# routeur_wemos_Maxi_v1_1c_2020-05-14_15-5.net
KiCad netlist of a schematic drawn in EasyEDA
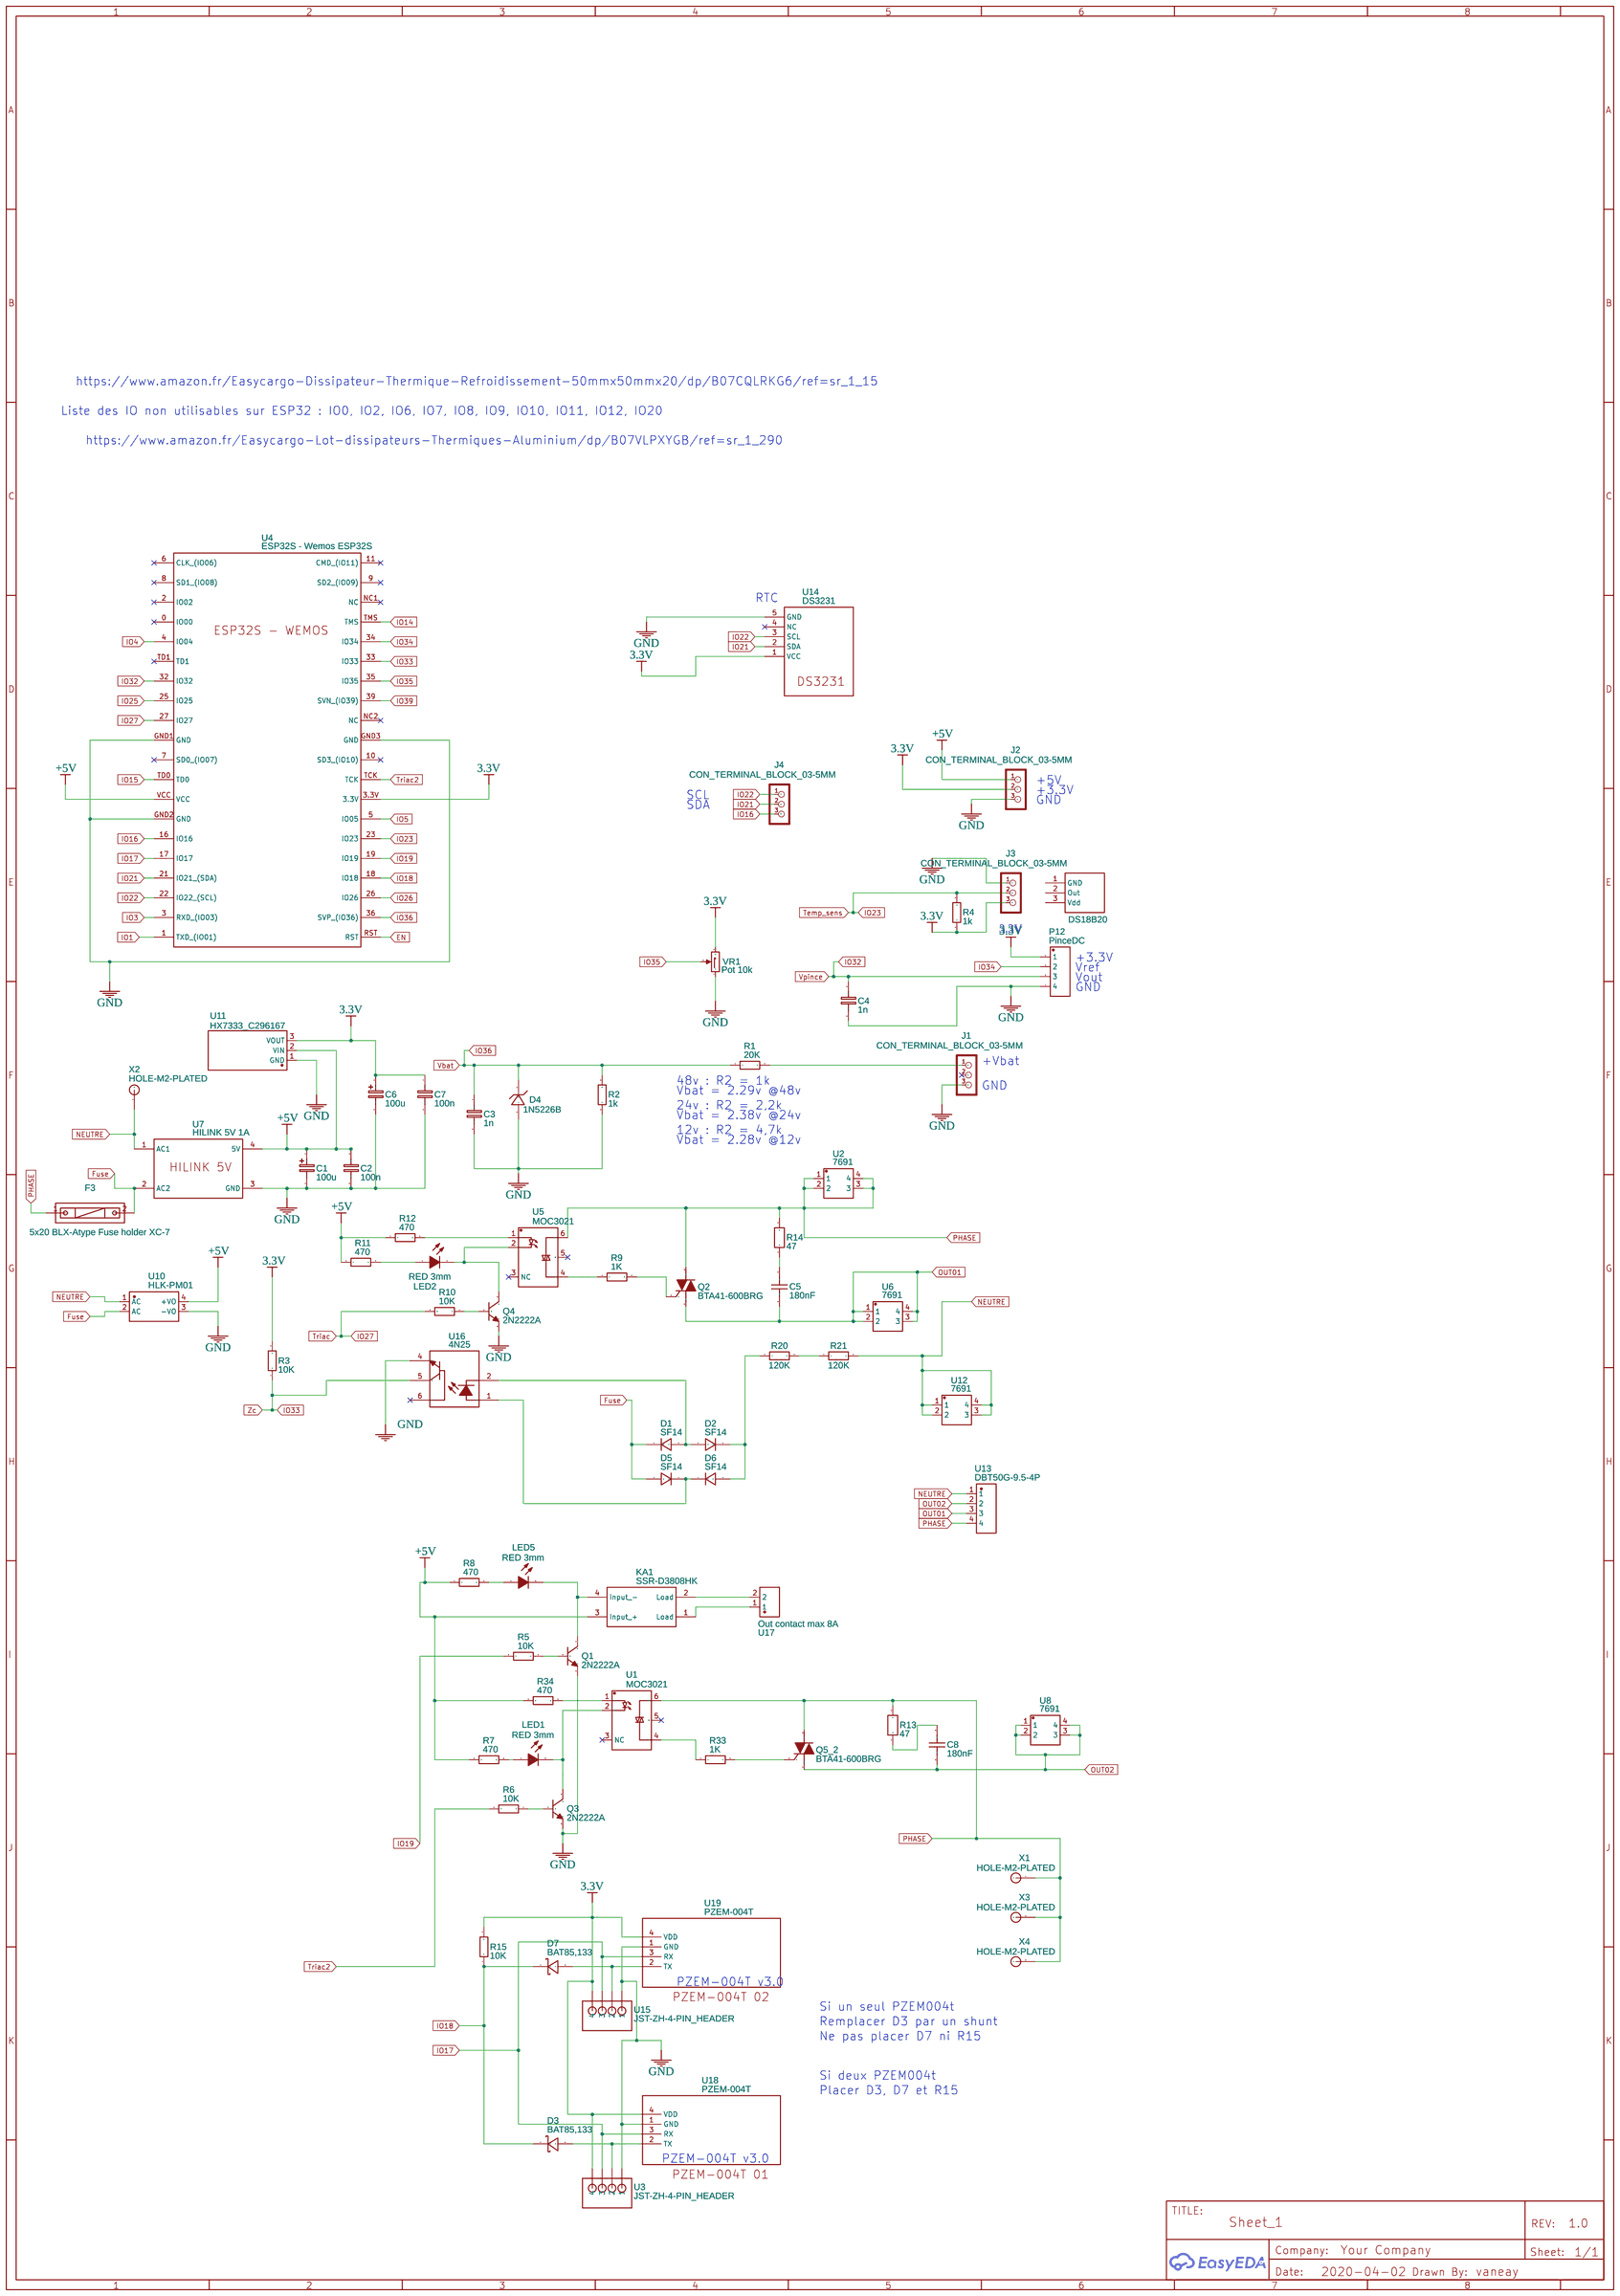
[diagram p0: schematic sheet]

(export (version "E")
  (design (tool "Eeschema 10.0.6"))
  (components
    (comp (ref "C1")
      (value "100u")
      (fields (field (name "BOM_Supplier Part") "C122609"))
      (libsource (lib "") (part "Cap_Electrolytic(TH)_D3.0XF1.5_EU"))
    )
    (comp (ref "C2")
      (value "100n")
      (fields (field (name "BOM_Supplier Part") "C94717"))
      (libsource (lib "") (part "Cap_RAD-0.1_EU"))
    )
    (comp (ref "C3")
      (value "1n")
      (fields (field (name "BOM_Supplier Part") "C192448"))
      (libsource (lib "") (part "Cap_RAD-0.1_EU"))
    )
    (comp (ref "C4")
      (value "1n")
      (fields (field (name "BOM_Supplier Part") "C192448"))
      (libsource (lib "") (part "Cap_RAD-0.1_EU_1"))
    )
    (comp (ref "C5")
      (value "180nF")
      (fields
        (field (name "BOM_Manufacturer Part") "SMXDX184KD2XXAB1515")
        (field (name "BOM_Supplier Part") "C155792")
      )
      (libsource (lib "") (part "SMXDX184KD2XXAB1515"))
    )
    (comp (ref "C6")
      (value "100u")
      (fields (field (name "BOM_Supplier Part") "C122609"))
      (libsource (lib "") (part "Cap_Electrolytic(TH)_D3.0XF1.5_EU"))
    )
    (comp (ref "C7")
      (value "100n")
      (fields (field (name "BOM_Supplier Part") "C94717"))
      (libsource (lib "") (part "Cap_RAD-0.1_EU"))
    )
    (comp (ref "C8")
      (value "180nF")
      (fields
        (field (name "BOM_Manufacturer Part") "SMXDX184KD2XXAB1515")
        (field (name "BOM_Supplier Part") "C155792")
      )
      (libsource (lib "") (part "SMXDX184KD2XXAB1515"))
    )
    (comp (ref "D1")
      (value "SF14")
      (fields (field (name "BOM_Supplier Part") "C331690"))
      (libsource (lib "") (part "SF14_1"))
    )
    (comp (ref "D2")
      (value "SF14")
      (fields (field (name "BOM_Supplier Part") "C331690"))
      (libsource (lib "") (part "SF14"))
    )
    (comp (ref "D3")
      (value "BAT85,133")
      (fields (field (name "BOM_Supplier Part") "C134301"))
      (libsource (lib "") (part "BAT85,133"))
    )
    (comp (ref "D4")
      (value "1N5226B")
      (fields (field (name "BOM_Supplier Part") "C51291"))
      (libsource (lib "") (part "1N751A"))
    )
    (comp (ref "D5")
      (value "SF14")
      (fields (field (name "BOM_Supplier Part") "C331690"))
      (libsource (lib "") (part "SF14"))
    )
    (comp (ref "D6")
      (value "SF14")
      (fields (field (name "BOM_Supplier Part") "C331690"))
      (libsource (lib "") (part "SF14_1"))
    )
    (comp (ref "D7")
      (value "BAT85,133")
      (fields (field (name "BOM_Supplier Part") "C134301"))
      (libsource (lib "") (part "BAT85,133"))
    )
    (comp (ref "F3")
      (value "5x20 BLX-Atype Fuse holder XC-7")
      (fields (field (name "BOM_Supplier Part") "C3131"))
      (libsource (lib "") (part "5x20 BLX-Atype Fuse holder XC-7"))
    )
    (comp (ref "J1")
      (value "CON_TERMINAL_BLOCK_03-5MM")
      (fields (field (name "BOM_Manufacturer Part") "?") (field (name "BOM_Supplier Part") "C182803"))
      (libsource (lib "") (part "Unknown_985_-425"))
    )
    (comp (ref "J2")
      (value "CON_TERMINAL_BLOCK_03-5MM")
      (fields (field (name "BOM_Manufacturer Part") "?") (field (name "BOM_Supplier Part") "C182803"))
      (libsource (lib "") (part "Unknown_1035_-715"))
    )
    (comp (ref "J3")
      (value "CON_TERMINAL_BLOCK_03-5MM")
      (fields (field (name "BOM_Manufacturer Part") "?") (field (name "BOM_Supplier Part") "C182803"))
      (libsource (lib "") (part "Unknown_1030_-610"))
    )
    (comp (ref "J4")
      (value "CON_TERMINAL_BLOCK_03-5MM")
      (fields (field (name "BOM_Manufacturer Part") "?") (field (name "BOM_Supplier Part") "C182803"))
      (libsource (lib "") (part "Unknown_795_-700"))
    )
    (comp (ref "KA1") (value "SSR-D3808HK") (libsource (lib "") (part "SSR-D3808HK")))
    (comp (ref "LED1")
      (value "RED 3mm")
      (fields
        (field (name "BOM_Manufacturer Part") "204-10SURD/S530-A3-L")
        (field (name "BOM_Supplier Part") "C99771")
      )
      (libsource (lib "") (part "204-10SURD/S530-A3-L"))
    )
    (comp (ref "LED2")
      (value "RED 3mm")
      (fields
        (field (name "BOM_Manufacturer Part") "204-10SURD/S530-A3-L")
        (field (name "BOM_Supplier Part") "C99771")
      )
      (libsource (lib "") (part "204-10SURD/S530-A3-L"))
    )
    (comp (ref "LED5")
      (value "RED 3mm")
      (fields
        (field (name "BOM_Manufacturer Part") "204-10SURD/S530-A3-L")
        (field (name "BOM_Supplier Part") "C99771")
      )
      (libsource (lib "") (part "204-10SURD/S530-A3-L"))
    )
    (comp (ref "P12")
      (value "PinceDC")
      (fields
        (field (name "BOM_Manufacturer Part") "EK508V-04P")
        (field (name "BOM_Supplier Part") "C182807")
      )
      (libsource (lib "") (part "WJ2EDGVC-5.08-4P"))
    )
    (comp (ref "Q1")
      (value "2N2222A")
      (fields (field (name "BOM_Supplier Part") "C358533"))
      (libsource (lib "") (part "2N2222A"))
    )
    (comp (ref "Q2")
      (value "BTA41-600BRG")
      (fields (field (name "BOM_Supplier Part") "C9103"))
      (libsource (lib "") (part "BTA41-600BRG"))
    )
    (comp (ref "Q3")
      (value "2N2222A")
      (fields (field (name "BOM_Supplier Part") "C358533"))
      (libsource (lib "") (part "2N2222A"))
    )
    (comp (ref "Q4")
      (value "2N2222A")
      (fields (field (name "BOM_Supplier Part") "C358533"))
      (libsource (lib "") (part "2N2222A"))
    )
    (comp (ref "Q5_2")
      (value "BTA41-600BRG")
      (fields (field (name "BOM_Supplier Part") "C9103"))
      (libsource (lib "") (part "BTA41-600BRG_1"))
    )
    (comp (ref "R1")
      (value "20K")
      (fields (field (name "BOM_Supplier Part") "C58592"))
      (libsource (lib "") (part "0805_2"))
    )
    (comp (ref "R2")
      (value "1k")
      (fields (field (name "BOM_Supplier Part") "C58592"))
      (libsource (lib "") (part "0805"))
    )
    (comp (ref "R3")
      (value "10K")
      (fields (field (name "BOM_Supplier Part") "C57436"))
      (libsource (lib "") (part "0805"))
    )
    (comp (ref "R4")
      (value "1k")
      (fields (field (name "BOM_Supplier Part") "C58592"))
      (libsource (lib "") (part "0805"))
    )
    (comp (ref "R5")
      (value "10K")
      (fields (field (name "BOM_Supplier Part") "C57436"))
      (libsource (lib "") (part "0805_1"))
    )
    (comp (ref "R6")
      (value "10K")
      (fields (field (name "BOM_Supplier Part") "C57436"))
      (libsource (lib "") (part "0805_1"))
    )
    (comp (ref "R7")
      (value "470")
      (fields (field (name "BOM_Supplier Part") "C58592"))
      (libsource (lib "") (part "0805_2"))
    )
    (comp (ref "R8")
      (value "470")
      (fields (field (name "BOM_Supplier Part") "C58592"))
      (libsource (lib "") (part "0805_2"))
    )
    (comp (ref "R9")
      (value "1K")
      (fields (field (name "BOM_Supplier Part") "C385291"))
      (libsource (lib "") (part "MFR1WSJT-52-5K1"))
    )
    (comp (ref "R10")
      (value "10K")
      (fields (field (name "BOM_Supplier Part") "C57436"))
      (libsource (lib "") (part "0805_1"))
    )
    (comp (ref "R11")
      (value "470")
      (fields (field (name "BOM_Supplier Part") "C58592"))
      (libsource (lib "") (part "0805_2"))
    )
    (comp (ref "R12")
      (value "470")
      (fields (field (name "BOM_Supplier Part") "C58592"))
      (libsource (lib "") (part "0805_2"))
    )
    (comp (ref "R13")
      (value "47")
      (fields
        (field (name "BOM_Manufacturer Part") "RN 2WS 47R F T/B A1")
        (field (name "BOM_Supplier Part") "C433590")
      )
      (libsource (lib "") (part "RN 2WS 47R F T/B A1"))
    )
    (comp (ref "R14")
      (value "47")
      (fields
        (field (name "BOM_Manufacturer Part") "RN 2WS 47R F T/B A1")
        (field (name "BOM_Supplier Part") "C433590")
      )
      (libsource (lib "") (part "RN 2WS 47R F T/B A1"))
    )
    (comp (ref "R15")
      (value "10K")
      (fields (field (name "BOM_Supplier Part") "C57436"))
      (libsource (lib "") (part "0805"))
    )
    (comp (ref "R20")
      (value "120K")
      (fields (field (name "BOM_Supplier Part") "C433673"))
      (libsource (lib "") (part "MFR1WSJT-52-5K1"))
    )
    (comp (ref "R21")
      (value "120K")
      (fields (field (name "BOM_Supplier Part") "C433673"))
      (libsource (lib "") (part "MFR1WSJT-52-5K1"))
    )
    (comp (ref "R33")
      (value "1K")
      (fields (field (name "BOM_Supplier Part") "C385291"))
      (libsource (lib "") (part "MFR1WSJT-52-5K1"))
    )
    (comp (ref "R34")
      (value "470")
      (fields (field (name "BOM_Supplier Part") "C58592"))
      (libsource (lib "") (part "0805_2"))
    )
    (comp (ref "U1")
      (value "MOC3021")
      (fields (field (name "BOM_Supplier Part") "C123202"))
      (libsource (lib "") (part "MOC3021"))
    )
    (comp (ref "U2")
      (value "7691")
      (fields (field (name "BOM_Supplier Part") "C238163"))
      (libsource (lib "") (part "7691"))
    )
    (comp (ref "U3")
      (value "JST-ZH-4-PIN_HEADER")
      (fields (field (name "BOM_Supplier Part") "C163034"))
      (libsource (lib "") (part "JST-ZH-4-PIN_HEADER"))
    )
    (comp (ref "U4")
      (value "ESP32S - Wemos ESP32S")
      (fields (field (name "BOM_Manufacturer Part") "ESP32S"))
      (libsource (lib "") (part "ESP32S - Wemos ESP32S"))
    )
    (comp (ref "U5")
      (value "MOC3021")
      (fields (field (name "BOM_Supplier Part") "C123202"))
      (libsource (lib "") (part "MOC3021_1"))
    )
    (comp (ref "U6")
      (value "7691")
      (fields (field (name "BOM_Supplier Part") "C238163"))
      (libsource (lib "") (part "7691"))
    )
    (comp (ref "U7")
      (value "HILINK 5V 1A")
      (fields (field (name "BOM_Manufacturer Part") "HLK-5M05") (field (name "BOM_Supplier Part") "C209907"))
      (libsource (lib "") (part "HILINK 5V corrected"))
    )
    (comp (ref "U8")
      (value "7691")
      (fields (field (name "BOM_Supplier Part") "C238163"))
      (libsource (lib "") (part "7691"))
    )
    (comp (ref "U9") (value "DS18B20") (libsource (lib "") (part "DS18B20")))
    (comp (ref "U10")
      (value "HLK-PM01")
      (fields (field (name "BOM_Supplier Part") "C209903"))
      (libsource (lib "") (part "HLK-PM01"))
    )
    (comp (ref "U11")
      (value "HX7333_C296167")
      (fields (field (name "BOM_Manufacturer Part") "HX7333") (field (name "BOM_Supplier Part") "C296167"))
      (libsource (lib "") (part "HX7333_C296167"))
    )
    (comp (ref "U12")
      (value "7691")
      (fields (field (name "BOM_Supplier Part") "C238163"))
      (libsource (lib "") (part "7691"))
    )
    (comp (ref "U13")
      (value "DBT50G-9.5-4P")
      (fields (field (name "BOM_Supplier Part") "C395960"))
      (libsource (lib "") (part "DBT50G-9.5-4P"))
    )
    (comp (ref "U14")
      (value "DS3231")
      (fields
        (field (name "BOM_Supplier Part") "https://www.amazon.fr/Delicacydex-dhorloge-arduino-Batterie-Raspberry/dp/B07P6RHHKX/ref=sr_1_2")
      )
      (libsource (lib "") (part "DS3231"))
    )
    (comp (ref "U15")
      (value "JST-ZH-4-PIN_HEADER")
      (fields (field (name "BOM_Supplier Part") "C163034"))
      (libsource (lib "") (part "JST-ZH-4-PIN_HEADER"))
    )
    (comp (ref "U16")
      (value "4N25")
      (fields (field (name "BOM_Supplier Part") "C115480"))
      (libsource (lib "") (part "4N25"))
    )
    (comp (ref "U17")
      (value "Out contact max 8A")
      (fields (field (name "BOM_Manufacturer Part") "282858-2") (field (name "BOM_Supplier Part") "C306150"))
      (libsource (lib "") (part "282858-2"))
    )
    (comp (ref "U18")
      (value "PZEM-004T")
      (fields (field (name "BOM_Manufacturer Part") "New SchematicLib"))
      (libsource (lib "") (part "PZEM-004T_1"))
    )
    (comp (ref "U19")
      (value "PZEM-004T")
      (fields (field (name "BOM_Manufacturer Part") "New SchematicLib"))
      (libsource (lib "") (part "PZEM-004T"))
    )
    (comp (ref "VR1") (value "Pot 10k") (libsource (lib "") (part "Pot")))
    (comp (ref "X1")
      (value "HOLE-M2-PLATED")
      (fields (field (name "BOM_Manufacturer Part") "New SchematicLib"))
      (libsource (lib "") (part "HOLE-M2-PLATED_1"))
    )
    (comp (ref "X2")
      (value "HOLE-M2-PLATED")
      (fields (field (name "BOM_Manufacturer Part") "New SchematicLib"))
      (libsource (lib "") (part "HOLE-M2-PLATED"))
    )
    (comp (ref "X3")
      (value "HOLE-M2-PLATED")
      (fields (field (name "BOM_Manufacturer Part") "New SchematicLib"))
      (libsource (lib "") (part "HOLE-M2-PLATED_1"))
    )
    (comp (ref "X4")
      (value "HOLE-M2-PLATED")
      (fields (field (name "BOM_Manufacturer Part") "New SchematicLib"))
      (libsource (lib "") (part "HOLE-M2-PLATED_1"))
    )
  )
  (nets
    (net (code "1") (name "+5V") (class "Default")
      (node (ref "C1") (pin "1") (pinfunction "1_1") (pintype "unspecified"))
      (node (ref "C2") (pin "1") (pinfunction "1_1") (pintype "unspecified"))
      (node (ref "J2") (pin "1") (pinfunction "1_1") (pintype "unspecified"))
      (node (ref "KA1") (pin "3") (pinfunction "Input_+_3") (pintype "unspecified"))
      (node (ref "R11") (pin "1") (pinfunction "1_1") (pintype "unspecified"))
      (node (ref "R12") (pin "1") (pinfunction "1_1") (pintype "unspecified"))
      (node (ref "R34") (pin "1") (pinfunction "1_1") (pintype "unspecified"))
      (node (ref "R7") (pin "1") (pinfunction "1_1") (pintype "unspecified"))
      (node (ref "R8") (pin "1") (pinfunction "1_1") (pintype "unspecified"))
      (node (ref "U10") (pin "4") (pinfunction "+VO_4") (pintype "unspecified"))
      (node (ref "U11") (pin "2") (pinfunction "VIN_2") (pintype "unspecified"))
      (node (ref "U4") (pin "VCC") (pinfunction "VCC_VCC") (pintype "unspecified"))
      (node (ref "U7") (pin "4") (pinfunction "5V_4") (pintype "unspecified"))
    )
    (net (code "2") (name "3.3V") (class "Default")
      (node (ref "C6") (pin "1") (pinfunction "1_1") (pintype "unspecified"))
      (node (ref "C7") (pin "1") (pinfunction "1_1") (pintype "unspecified"))
      (node (ref "J2") (pin "2") (pinfunction "2_2") (pintype "unspecified"))
      (node (ref "J3") (pin "3") (pinfunction "3_3") (pintype "unspecified"))
      (node (ref "P12") (pin "1") (pinfunction "1_1") (pintype "unspecified"))
      (node (ref "R15") (pin "2") (pinfunction "2_2") (pintype "unspecified"))
      (node (ref "R3") (pin "2") (pinfunction "2_2") (pintype "unspecified"))
      (node (ref "R4") (pin "1") (pinfunction "1_1") (pintype "unspecified"))
      (node (ref "U11") (pin "3") (pinfunction "VOUT_3") (pintype "unspecified"))
      (node (ref "U14") (pin "1") (pinfunction "VCC_1") (pintype "unspecified"))
      (node (ref "U15") (pin "P4") (pinfunction "4_P4") (pintype "unspecified"))
      (node (ref "U18") (pin "4") (pinfunction "VDD_4") (pintype "unspecified"))
      (node (ref "U19") (pin "4") (pinfunction "VDD_4") (pintype "unspecified"))
      (node (ref "U3") (pin "P4") (pinfunction "4_P4") (pintype "unspecified"))
      (node (ref "U4") (pin "3.3V") (pinfunction "3.3V_3.3V") (pintype "unspecified"))
      (node (ref "VR1") (pin "3") (pinfunction "3_3") (pintype "unspecified"))
    )
    (net (code "3") (name "EN") (class "Default")
      (node (ref "U4") (pin "RST") (pinfunction "RST_RST") (pintype "unspecified"))
    )
    (net (code "4") (name "Fuse") (class "Default")
      (node (ref "D1") (pin "1") (pinfunction "1_1") (pintype "unspecified"))
      (node (ref "D5") (pin "2") (pinfunction "2_2") (pintype "unspecified"))
      (node (ref "F3") (pin "2") (pinfunction "2_2") (pintype "unspecified"))
      (node (ref "U10") (pin "2") (pinfunction "AC_2") (pintype "unspecified"))
      (node (ref "U7") (pin "2") (pinfunction "AC2_2") (pintype "unspecified"))
    )
    (net (code "5") (name "GND") (class "Default")
      (node (ref "C1") (pin "2") (pinfunction "2_2") (pintype "unspecified"))
      (node (ref "C2") (pin "2") (pinfunction "2_2") (pintype "unspecified"))
      (node (ref "C3") (pin "2") (pinfunction "2_2") (pintype "unspecified"))
      (node (ref "C4") (pin "2") (pinfunction "2_2") (pintype "unspecified"))
      (node (ref "C6") (pin "2") (pinfunction "2_2") (pintype "unspecified"))
      (node (ref "C7") (pin "2") (pinfunction "2_2") (pintype "unspecified"))
      (node (ref "D4") (pin "2") (pinfunction "A_2") (pintype "unspecified"))
      (node (ref "J1") (pin "3") (pinfunction "3_3") (pintype "unspecified"))
      (node (ref "J2") (pin "3") (pinfunction "3_3") (pintype "unspecified"))
      (node (ref "J3") (pin "1") (pinfunction "1_1") (pintype "unspecified"))
      (node (ref "P12") (pin "4") (pinfunction "4_4") (pintype "unspecified"))
      (node (ref "Q1") (pin "3") (pinfunction "E_3") (pintype "unspecified"))
      (node (ref "Q3") (pin "3") (pinfunction "E_3") (pintype "unspecified"))
      (node (ref "Q4") (pin "3") (pinfunction "E_3") (pintype "unspecified"))
      (node (ref "R2") (pin "1") (pinfunction "1_1") (pintype "unspecified"))
      (node (ref "U10") (pin "3") (pinfunction "-VO_3") (pintype "unspecified"))
      (node (ref "U11") (pin "1") (pinfunction "GND_1") (pintype "unspecified"))
      (node (ref "U14") (pin "5") (pinfunction "GND_5") (pintype "unspecified"))
      (node (ref "U15") (pin "P1") (pinfunction "1_P1") (pintype "unspecified"))
      (node (ref "U16") (pin "4") (pinfunction "4_4") (pintype "unspecified"))
      (node (ref "U18") (pin "1") (pinfunction "GND_1") (pintype "unspecified"))
      (node (ref "U19") (pin "1") (pinfunction "GND_1") (pintype "unspecified"))
      (node (ref "U3") (pin "P1") (pinfunction "1_P1") (pintype "unspecified"))
      (node (ref "U4") (pin "GND1") (pinfunction "GND_GND1") (pintype "unspecified"))
      (node (ref "U4") (pin "GND2") (pinfunction "GND_GND2") (pintype "unspecified"))
      (node (ref "U4") (pin "GND3") (pinfunction "GND_GND3") (pintype "unspecified"))
      (node (ref "U7") (pin "3") (pinfunction "GND_3") (pintype "unspecified"))
      (node (ref "VR1") (pin "1") (pinfunction "1_1") (pintype "unspecified"))
    )
    (net (code "6") (name "IO1") (class "Default")
      (node (ref "U4") (pin "1") (pinfunction "TXD_(IO01)_1") (pintype "unspecified"))
    )
    (net (code "7") (name "IO3") (class "Default")
      (node (ref "U4") (pin "3") (pinfunction "RXD_(IO03)_3") (pintype "unspecified"))
    )
    (net (code "8") (name "IO4") (class "Default")
      (node (ref "U4") (pin "4") (pinfunction "IO04_4") (pintype "unspecified"))
    )
    (net (code "9") (name "IO5") (class "Default")
      (node (ref "U4") (pin "5") (pinfunction "IO05_5") (pintype "unspecified"))
    )
    (net (code "10") (name "IO14") (class "Default")
      (node (ref "U4") (pin "TMS") (pinfunction "TMS_TMS") (pintype "unspecified"))
    )
    (net (code "11") (name "IO15") (class "Default")
      (node (ref "U4") (pin "TD0") (pinfunction "TD0_TD0") (pintype "unspecified"))
    )
    (net (code "12") (name "IO16") (class "Default")
      (node (ref "J4") (pin "3") (pinfunction "3_3") (pintype "unspecified"))
      (node (ref "U4") (pin "16") (pinfunction "IO16_16") (pintype "unspecified"))
    )
    (net (code "13") (name "IO17") (class "Default")
      (node (ref "U15") (pin "P3") (pinfunction "3_P3") (pintype "unspecified"))
      (node (ref "U18") (pin "3") (pinfunction "RX_3") (pintype "unspecified"))
      (node (ref "U19") (pin "3") (pinfunction "RX_3") (pintype "unspecified"))
      (node (ref "U3") (pin "P3") (pinfunction "3_P3") (pintype "unspecified"))
      (node (ref "U4") (pin "17") (pinfunction "IO17_17") (pintype "unspecified"))
    )
    (net (code "14") (name "IO18") (class "Default")
      (node (ref "D3") (pin "1") (pinfunction "K_1") (pintype "unspecified"))
      (node (ref "D7") (pin "1") (pinfunction "K_1") (pintype "unspecified"))
      (node (ref "R15") (pin "1") (pinfunction "1_1") (pintype "unspecified"))
      (node (ref "U4") (pin "18") (pinfunction "IO18_18") (pintype "unspecified"))
    )
    (net (code "15") (name "IO19") (class "Default")
      (node (ref "R5") (pin "2") (pinfunction "2_2") (pintype "unspecified"))
      (node (ref "U4") (pin "19") (pinfunction "IO19_19") (pintype "unspecified"))
    )
    (net (code "16") (name "IO21") (class "Default")
      (node (ref "J4") (pin "2") (pinfunction "2_2") (pintype "unspecified"))
      (node (ref "U14") (pin "2") (pinfunction "SDA_2") (pintype "unspecified"))
      (node (ref "U4") (pin "21") (pinfunction "IO21_(SDA)_21") (pintype "unspecified"))
    )
    (net (code "17") (name "IO22") (class "Default")
      (node (ref "J4") (pin "1") (pinfunction "1_1") (pintype "unspecified"))
      (node (ref "U14") (pin "3") (pinfunction "SCL_3") (pintype "unspecified"))
      (node (ref "U4") (pin "22") (pinfunction "IO22_(SCL)_22") (pintype "unspecified"))
    )
    (net (code "18") (name "IO23") (class "Default")
      (node (ref "J3") (pin "2") (pinfunction "2_2") (pintype "unspecified"))
      (node (ref "R4") (pin "2") (pinfunction "2_2") (pintype "unspecified"))
      (node (ref "U4") (pin "23") (pinfunction "IO23_23") (pintype "unspecified"))
    )
    (net (code "19") (name "IO25") (class "Default")
      (node (ref "U4") (pin "25") (pinfunction "IO25_25") (pintype "unspecified"))
    )
    (net (code "20") (name "IO26") (class "Default")
      (node (ref "U4") (pin "26") (pinfunction "IO26_26") (pintype "unspecified"))
    )
    (net (code "21") (name "IO27") (class "Default")
      (node (ref "R10") (pin "2") (pinfunction "2_2") (pintype "unspecified"))
      (node (ref "U4") (pin "27") (pinfunction "IO27_27") (pintype "unspecified"))
    )
    (net (code "22") (name "IO32") (class "Default")
      (node (ref "C4") (pin "1") (pinfunction "1_1") (pintype "unspecified"))
      (node (ref "P12") (pin "3") (pinfunction "3_3") (pintype "unspecified"))
      (node (ref "U4") (pin "32") (pinfunction "IO32_32") (pintype "unspecified"))
    )
    (net (code "23") (name "IO33") (class "Default")
      (node (ref "R3") (pin "1") (pinfunction "1_1") (pintype "unspecified"))
      (node (ref "U16") (pin "5") (pinfunction "5_5") (pintype "unspecified"))
      (node (ref "U4") (pin "33") (pinfunction "IO33_33") (pintype "unspecified"))
    )
    (net (code "24") (name "IO34") (class "Default")
      (node (ref "P12") (pin "2") (pinfunction "2_2") (pintype "unspecified"))
      (node (ref "U4") (pin "34") (pinfunction "IO34_34") (pintype "unspecified"))
    )
    (net (code "25") (name "IO35") (class "Default")
      (node (ref "U4") (pin "35") (pinfunction "IO35_35") (pintype "unspecified"))
      (node (ref "VR1") (pin "2") (pinfunction "2_2") (pintype "unspecified"))
    )
    (net (code "26") (name "IO36") (class "Default")
      (node (ref "C3") (pin "1") (pinfunction "1_1") (pintype "unspecified"))
      (node (ref "D4") (pin "1") (pinfunction "C_1") (pintype "unspecified"))
      (node (ref "R1") (pin "1") (pinfunction "1_1") (pintype "unspecified"))
      (node (ref "R2") (pin "2") (pinfunction "2_2") (pintype "unspecified"))
      (node (ref "U4") (pin "36") (pinfunction "SVP_(IO36)_36") (pintype "unspecified"))
    )
    (net (code "27") (name "IO39") (class "Default")
      (node (ref "U4") (pin "39") (pinfunction "SVN_(IO39)_39") (pintype "unspecified"))
    )
    (net (code "28") (name "NEUTRE") (class "Default")
      (node (ref "R21") (pin "2") (pinfunction "2_2") (pintype "unspecified"))
      (node (ref "U10") (pin "1") (pinfunction "AC_1") (pintype "unspecified"))
      (node (ref "U12") (pin "1") (pinfunction "1_1") (pintype "unspecified"))
      (node (ref "U12") (pin "2") (pinfunction "2_2") (pintype "unspecified"))
      (node (ref "U12") (pin "3") (pinfunction "3_3") (pintype "unspecified"))
      (node (ref "U12") (pin "4") (pinfunction "4_4") (pintype "unspecified"))
      (node (ref "U13") (pin "1") (pinfunction "1_1") (pintype "unspecified"))
      (node (ref "U7") (pin "1") (pinfunction "AC1_1") (pintype "unspecified"))
      (node (ref "X2") (pin "1") (pinfunction "1_1") (pintype "unspecified"))
    )
    (net (code "29") (name "Net-(C5-Pad1)") (class "Default")
      (node (ref "C5") (pin "1") (pinfunction "1_1") (pintype "unspecified"))
      (node (ref "R14") (pin "1") (pinfunction "1_1") (pintype "unspecified"))
    )
    (net (code "30") (name "Net-(C8-Pad1)") (class "Default")
      (node (ref "C8") (pin "1") (pinfunction "1_1") (pintype "unspecified"))
      (node (ref "R13") (pin "1") (pinfunction "1_1") (pintype "unspecified"))
    )
    (net (code "31") (name "Net-(D1-Pad2)") (class "Default")
      (node (ref "D1") (pin "2") (pinfunction "2_2") (pintype "unspecified"))
      (node (ref "D2") (pin "2") (pinfunction "2_2") (pintype "unspecified"))
      (node (ref "U16") (pin "2") (pinfunction "2_2") (pintype "unspecified"))
    )
    (net (code "32") (name "Net-(D2-Pad1)") (class "Default")
      (node (ref "D2") (pin "1") (pinfunction "1_1") (pintype "unspecified"))
      (node (ref "D6") (pin "2") (pinfunction "2_2") (pintype "unspecified"))
      (node (ref "R20") (pin "1") (pinfunction "1_1") (pintype "unspecified"))
    )
    (net (code "33") (name "Net-(D3-A)") (class "Default")
      (node (ref "D3") (pin "2") (pinfunction "A_2") (pintype "unspecified"))
      (node (ref "U18") (pin "2") (pinfunction "TX_2") (pintype "unspecified"))
      (node (ref "U3") (pin "P2") (pinfunction "2_P2") (pintype "unspecified"))
    )
    (net (code "34") (name "Net-(D5-Pad1)") (class "Default")
      (node (ref "D5") (pin "1") (pinfunction "1_1") (pintype "unspecified"))
      (node (ref "D6") (pin "1") (pinfunction "1_1") (pintype "unspecified"))
      (node (ref "U16") (pin "1") (pinfunction "1_1") (pintype "unspecified"))
    )
    (net (code "35") (name "Net-(D7-A)") (class "Default")
      (node (ref "D7") (pin "2") (pinfunction "A_2") (pintype "unspecified"))
      (node (ref "U15") (pin "P2") (pinfunction "2_P2") (pintype "unspecified"))
      (node (ref "U19") (pin "2") (pinfunction "TX_2") (pintype "unspecified"))
    )
    (net (code "36") (name "Net-(J1-Pad1)") (class "Default")
      (node (ref "J1") (pin "1") (pinfunction "1_1") (pintype "unspecified"))
      (node (ref "R1") (pin "2") (pinfunction "2_2") (pintype "unspecified"))
    )
    (net (code "37") (name "Net-(KA1-Input_-)") (class "Default")
      (node (ref "KA1") (pin "4") (pinfunction "Input_-_4") (pintype "unspecified"))
      (node (ref "LED5") (pin "2") (pinfunction "K_2") (pintype "input"))
      (node (ref "Q1") (pin "1") (pinfunction "C_1") (pintype "unspecified"))
    )
    (net (code "38") (name "Net-(KA1-Load-Pad1)") (class "Default")
      (node (ref "KA1") (pin "1") (pinfunction "Load_1") (pintype "unspecified"))
      (node (ref "U17") (pin "1") (pinfunction "1_1") (pintype "unspecified"))
    )
    (net (code "39") (name "Net-(KA1-Load-Pad2)") (class "Default")
      (node (ref "KA1") (pin "2") (pinfunction "Load_2") (pintype "unspecified"))
      (node (ref "U17") (pin "2") (pinfunction "2_2") (pintype "unspecified"))
    )
    (net (code "40") (name "Net-(LED1-A)") (class "Default")
      (node (ref "LED1") (pin "1") (pinfunction "A_1") (pintype "input"))
      (node (ref "R7") (pin "2") (pinfunction "2_2") (pintype "unspecified"))
    )
    (net (code "41") (name "Net-(LED1-K)") (class "Default")
      (node (ref "LED1") (pin "2") (pinfunction "K_2") (pintype "input"))
      (node (ref "Q3") (pin "1") (pinfunction "C_1") (pintype "unspecified"))
      (node (ref "U1") (pin "2") (pinfunction "2_2") (pintype "unspecified"))
    )
    (net (code "42") (name "Net-(LED2-A)") (class "Default")
      (node (ref "LED2") (pin "1") (pinfunction "A_1") (pintype "input"))
      (node (ref "R11") (pin "2") (pinfunction "2_2") (pintype "unspecified"))
    )
    (net (code "43") (name "Net-(LED2-K)") (class "Default")
      (node (ref "LED2") (pin "2") (pinfunction "K_2") (pintype "input"))
      (node (ref "Q4") (pin "1") (pinfunction "C_1") (pintype "unspecified"))
      (node (ref "U5") (pin "2") (pinfunction "2_2") (pintype "unspecified"))
    )
    (net (code "44") (name "Net-(LED5-A)") (class "Default")
      (node (ref "LED5") (pin "1") (pinfunction "A_1") (pintype "input"))
      (node (ref "R8") (pin "2") (pinfunction "2_2") (pintype "unspecified"))
    )
    (net (code "45") (name "Net-(Q1-B)") (class "Default")
      (node (ref "Q1") (pin "2") (pinfunction "B_2") (pintype "unspecified"))
      (node (ref "R5") (pin "1") (pinfunction "1_1") (pintype "unspecified"))
    )
    (net (code "46") (name "Net-(Q2-G)") (class "Default")
      (node (ref "Q2") (pin "3") (pinfunction "G_3") (pintype "unspecified"))
      (node (ref "R9") (pin "2") (pinfunction "2_2") (pintype "unspecified"))
    )
    (net (code "47") (name "Net-(Q3-B)") (class "Default")
      (node (ref "Q3") (pin "2") (pinfunction "B_2") (pintype "unspecified"))
      (node (ref "R6") (pin "1") (pinfunction "1_1") (pintype "unspecified"))
    )
    (net (code "48") (name "Net-(Q4-B)") (class "Default")
      (node (ref "Q4") (pin "2") (pinfunction "B_2") (pintype "unspecified"))
      (node (ref "R10") (pin "1") (pinfunction "1_1") (pintype "unspecified"))
    )
    (net (code "49") (name "Net-(Q5_2-G)") (class "Default")
      (node (ref "Q5_2") (pin "3") (pinfunction "G_3") (pintype "unspecified"))
      (node (ref "R33") (pin "2") (pinfunction "2_2") (pintype "unspecified"))
    )
    (net (code "50") (name "Net-(R12-Pad2)") (class "Default")
      (node (ref "R12") (pin "2") (pinfunction "2_2") (pintype "unspecified"))
      (node (ref "U5") (pin "1") (pinfunction "1_1") (pintype "unspecified"))
    )
    (net (code "51") (name "Net-(R20-Pad2)") (class "Default")
      (node (ref "R20") (pin "2") (pinfunction "2_2") (pintype "unspecified"))
      (node (ref "R21") (pin "1") (pinfunction "1_1") (pintype "unspecified"))
    )
    (net (code "52") (name "Net-(R34-Pad2)") (class "Default")
      (node (ref "R34") (pin "2") (pinfunction "2_2") (pintype "unspecified"))
      (node (ref "U1") (pin "1") (pinfunction "1_1") (pintype "unspecified"))
    )
    (net (code "53") (name "Net-(U1-E)") (class "Default")
      (node (ref "R33") (pin "1") (pinfunction "1_1") (pintype "unspecified"))
      (node (ref "U1") (pin "4") (pinfunction "E_4") (pintype "unspecified"))
    )
    (net (code "54") (name "Net-(U5-E)") (class "Default")
      (node (ref "R9") (pin "1") (pinfunction "1_1") (pintype "unspecified"))
      (node (ref "U5") (pin "4") (pinfunction "E_4") (pintype "unspecified"))
    )
    (net (code "55") (name "OUT01") (class "Default")
      (node (ref "C5") (pin "2") (pinfunction "2_2") (pintype "unspecified"))
      (node (ref "Q2") (pin "1") (pinfunction "M1_1") (pintype "unspecified"))
      (node (ref "U13") (pin "3") (pinfunction "3_3") (pintype "unspecified"))
      (node (ref "U6") (pin "1") (pinfunction "1_1") (pintype "unspecified"))
      (node (ref "U6") (pin "2") (pinfunction "2_2") (pintype "unspecified"))
      (node (ref "U6") (pin "3") (pinfunction "3_3") (pintype "unspecified"))
      (node (ref "U6") (pin "4") (pinfunction "4_4") (pintype "unspecified"))
    )
    (net (code "56") (name "OUT02") (class "Default")
      (node (ref "C8") (pin "2") (pinfunction "2_2") (pintype "unspecified"))
      (node (ref "Q5_2") (pin "1") (pinfunction "M1_1") (pintype "unspecified"))
      (node (ref "U13") (pin "2") (pinfunction "2_2") (pintype "unspecified"))
      (node (ref "U8") (pin "1") (pinfunction "1_1") (pintype "unspecified"))
      (node (ref "U8") (pin "2") (pinfunction "2_2") (pintype "unspecified"))
      (node (ref "U8") (pin "3") (pinfunction "3_3") (pintype "unspecified"))
      (node (ref "U8") (pin "4") (pinfunction "4_4") (pintype "unspecified"))
    )
    (net (code "57") (name "PHASE") (class "Default")
      (node (ref "F3") (pin "1") (pinfunction "1_1") (pintype "unspecified"))
      (node (ref "Q2") (pin "2") (pinfunction "M2_2") (pintype "unspecified"))
      (node (ref "Q5_2") (pin "2") (pinfunction "M2_2") (pintype "unspecified"))
      (node (ref "R13") (pin "2") (pinfunction "2_2") (pintype "unspecified"))
      (node (ref "R14") (pin "2") (pinfunction "2_2") (pintype "unspecified"))
      (node (ref "U1") (pin "6") (pinfunction "BASE_6") (pintype "unspecified"))
      (node (ref "U13") (pin "4") (pinfunction "4_4") (pintype "unspecified"))
      (node (ref "U2") (pin "1") (pinfunction "1_1") (pintype "unspecified"))
      (node (ref "U2") (pin "2") (pinfunction "2_2") (pintype "unspecified"))
      (node (ref "U2") (pin "3") (pinfunction "3_3") (pintype "unspecified"))
      (node (ref "U2") (pin "4") (pinfunction "4_4") (pintype "unspecified"))
      (node (ref "U5") (pin "6") (pinfunction "BASE_6") (pintype "unspecified"))
      (node (ref "X1") (pin "1") (pinfunction "1_1") (pintype "unspecified"))
      (node (ref "X3") (pin "1") (pinfunction "1_1") (pintype "unspecified"))
      (node (ref "X4") (pin "1") (pinfunction "1_1") (pintype "unspecified"))
    )
    (net (code "58") (name "Triac2") (class "Default")
      (node (ref "R6") (pin "2") (pinfunction "2_2") (pintype "unspecified"))
      (node (ref "U4") (pin "TCK") (pinfunction "TCK_TCK") (pintype "unspecified"))
    )
    (net (code "59") (name "unconnected-(J1-Pad2)") (class "Default")
      (node (ref "J1") (pin "2") (pinfunction "2_2") (pintype "unspecified+no_connect"))
    )
    (net (code "60") (name "unconnected-(U1-NC-Pad3)") (class "Default")
      (node (ref "U1") (pin "3") (pinfunction "NC_3") (pintype "unspecified+no_connect"))
    )
    (net (code "61") (name "unconnected-(U1-SUB-Pad5)") (class "Default")
      (node (ref "U1") (pin "5") (pinfunction "SUB_5") (pintype "unspecified+no_connect"))
    )
    (net (code "62") (name "unconnected-(U4-CLK_(IO06)-Pad6)") (class "Default")
      (node (ref "U4") (pin "6") (pinfunction "CLK_(IO06)_6") (pintype "unspecified+no_connect"))
    )
    (net (code "63") (name "unconnected-(U4-CMD_(IO11)-Pad11)") (class "Default")
      (node (ref "U4") (pin "11") (pinfunction "CMD_(IO11)_11") (pintype "unspecified+no_connect"))
    )
    (net (code "64") (name "unconnected-(U4-IO00-Pad0)") (class "Default")
      (node (ref "U4") (pin "0") (pinfunction "IO00_0") (pintype "unspecified+no_connect"))
    )
    (net (code "65") (name "unconnected-(U4-IO02-Pad2)") (class "Default")
      (node (ref "U4") (pin "2") (pinfunction "IO02_2") (pintype "unspecified+no_connect"))
    )
    (net (code "66") (name "unconnected-(U4-NC-PadNC1)") (class "Default")
      (node (ref "U4") (pin "NC1") (pinfunction "NC_NC1") (pintype "unspecified+no_connect"))
    )
    (net (code "67") (name "unconnected-(U4-NC-PadNC2)") (class "Default")
      (node (ref "U4") (pin "NC2") (pinfunction "NC_NC2") (pintype "unspecified+no_connect"))
    )
    (net (code "68") (name "unconnected-(U4-PadTD1)") (class "Default")
      (node (ref "U4") (pin "TD1") (pinfunction "TD1_TD1") (pintype "unspecified+no_connect"))
    )
    (net (code "69") (name "unconnected-(U4-SD0_(IO07)-Pad7)") (class "Default")
      (node (ref "U4") (pin "7") (pinfunction "SD0_(IO07)_7") (pintype "unspecified+no_connect"))
    )
    (net (code "70") (name "unconnected-(U4-SD1_(IO08)-Pad8)") (class "Default")
      (node (ref "U4") (pin "8") (pinfunction "SD1_(IO08)_8") (pintype "unspecified+no_connect"))
    )
    (net (code "71") (name "unconnected-(U4-SD2_(IO09)-Pad9)") (class "Default")
      (node (ref "U4") (pin "9") (pinfunction "SD2_(IO09)_9") (pintype "unspecified+no_connect"))
    )
    (net (code "72") (name "unconnected-(U4-SD3_(IO10)-Pad10)") (class "Default")
      (node (ref "U4") (pin "10") (pinfunction "SD3_(IO10)_10") (pintype "unspecified+no_connect"))
    )
    (net (code "73") (name "unconnected-(U5-NC-Pad3)") (class "Default")
      (node (ref "U5") (pin "3") (pinfunction "NC_3") (pintype "unspecified+no_connect"))
    )
    (net (code "74") (name "unconnected-(U5-SUB-Pad5)") (class "Default")
      (node (ref "U5") (pin "5") (pinfunction "SUB_5") (pintype "unspecified+no_connect"))
    )
    (net (code "75") (name "unconnected-(U9-GND-Pad1)") (class "Default")
      (node (ref "U9") (pin "1") (pinfunction "GND_1") (pintype "unspecified"))
    )
    (net (code "76") (name "unconnected-(U9-Out-Pad2)") (class "Default")
      (node (ref "U9") (pin "2") (pinfunction "Out_2") (pintype "unspecified"))
    )
    (net (code "77") (name "unconnected-(U9-Vdd-Pad3)") (class "Default")
      (node (ref "U9") (pin "3") (pinfunction "Vdd_3") (pintype "unspecified"))
    )
    (net (code "78") (name "unconnected-(U14-NC-Pad4)") (class "Default")
      (node (ref "U14") (pin "4") (pinfunction "NC_4") (pintype "unspecified+no_connect"))
    )
    (net (code "79") (name "unconnected-(U16-Pad6)") (class "Default")
      (node (ref "U16") (pin "6") (pinfunction "6_6") (pintype "unspecified+no_connect"))
    )
  )
)
